# DEBUG.net
KiCad netlist of a schematic drawn in Altium Designer
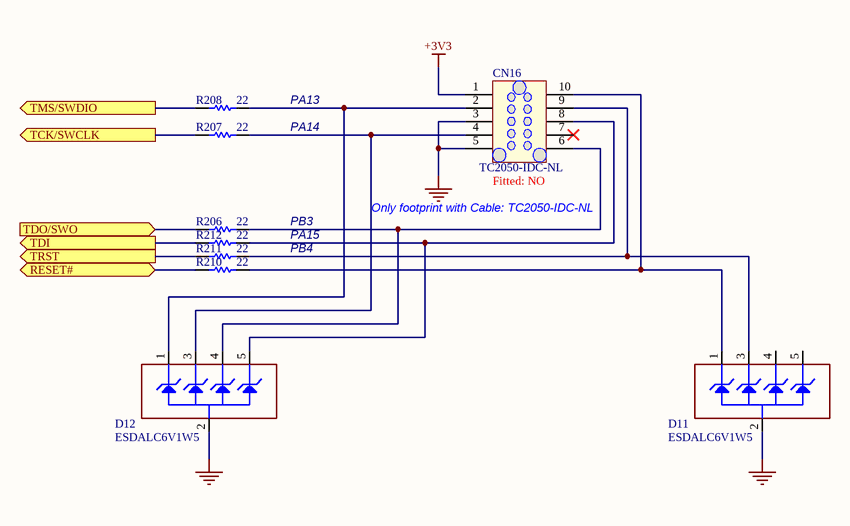
[diagram p0: DEBUG.SchDoc]

(export (version "E")
  (design (tool "Eeschema 10.0.6"))
  (components
    (comp (ref "CN16")
      (value "TC2050-IDC-NL")
      (footprint "TC2050-IDC-NL")
      (description "Tag_Connector Header, 10-Pin, Dual row No legs")
      (fields (field (name "FITTED") "NO"))
      (libsource (lib "MCD_TEMP_PCH") (part "Tag-10-C"))
    )
    (comp (ref "D11")
      (value "ESDALC6V1W5")
      (footprint "SC70-5")
      (description "Dual Transil array for ESD protection")
      (libsource (lib "MB1167_1") (part "ESDALC6V1W5"))
    )
    (comp (ref "D12")
      (value "ESDALC6V1W5")
      (footprint "SC70-5")
      (description "Dual Transil array for ESD protection")
      (libsource (lib "MB1167_1") (part "ESDALC6V1W5"))
    )
    (comp (ref "R206")
      (value "22")
      (footprint "0603R")
      (description "Resistor")
      (fields (field (name "PUBLISHER") "Altium Limited"))
      (libsource (lib "Miscellaneous Devices") (part "Res1"))
    )
    (comp (ref "R207")
      (value "22")
      (footprint "0603R")
      (description "Resistor")
      (fields (field (name "PUBLISHER") "Altium Limited"))
      (libsource (lib "Miscellaneous Devices") (part "Res1"))
    )
    (comp (ref "R208")
      (value "22")
      (footprint "0603R")
      (description "Resistor")
      (fields (field (name "PUBLISHER") "Altium Limited"))
      (libsource (lib "Miscellaneous Devices") (part "Res1"))
    )
    (comp (ref "R210")
      (value "22")
      (footprint "0603R")
      (description "Resistor")
      (fields (field (name "PUBLISHER") "Altium Limited"))
      (libsource (lib "Miscellaneous Devices") (part "Res1"))
    )
    (comp (ref "R211")
      (value "22")
      (footprint "0603R")
      (description "Resistor")
      (fields (field (name "PUBLISHER") "Altium Limited"))
      (libsource (lib "Miscellaneous Devices") (part "Res1"))
    )
    (comp (ref "R212")
      (value "22")
      (footprint "0603R")
      (description "Resistor")
      (fields (field (name "PUBLISHER") "Altium Limited"))
      (libsource (lib "Miscellaneous Devices") (part "Res1"))
    )
  )
  (nets
    (net (code "1") (name "+3V3") (class "Default")
      (node (ref "CN16") (pin "1") (pinfunction "1_1") (pintype "passive"))
    )
    (net (code "2") (name "/RESET#") (class "Default")
      (node (ref "R210") (pin "2") (pinfunction "2_2") (pintype "passive"))
    )
    (net (code "3") (name "/TCK{slash}SWCLK") (class "Default")
      (node (ref "R207") (pin "2") (pinfunction "2_2") (pintype "passive"))
    )
    (net (code "4") (name "/TDI") (class "Default")
      (node (ref "R212") (pin "2") (pinfunction "2_2") (pintype "passive"))
    )
    (net (code "5") (name "/TDO{slash}SWO") (class "Default")
      (node (ref "R206") (pin "2") (pinfunction "2_2") (pintype "passive"))
    )
    (net (code "6") (name "/TMS{slash}SWDIO") (class "Default")
      (node (ref "R208") (pin "2") (pinfunction "2_2") (pintype "passive"))
    )
    (net (code "7") (name "/TRST") (class "Default")
      (node (ref "R211") (pin "2") (pinfunction "2_2") (pintype "passive"))
    )
    (net (code "8") (name "GND") (class "Default")
      (node (ref "CN16") (pin "3") (pinfunction "3_3") (pintype "passive"))
      (node (ref "CN16") (pin "5") (pinfunction "5_5") (pintype "passive"))
      (node (ref "D11") (pin "2") (pinfunction "GND_2") (pintype "passive"))
      (node (ref "D12") (pin "2") (pinfunction "GND_2") (pintype "passive"))
    )
    (net (code "9") (name "Net-(D11-IO1)") (class "Default")
      (node (ref "CN16") (pin "10") (pinfunction "10_10") (pintype "passive"))
      (node (ref "D11") (pin "1") (pinfunction "IO1_1") (pintype "passive"))
      (node (ref "R210") (pin "1") (pinfunction "1_1") (pintype "passive"))
    )
    (net (code "10") (name "Net-(D11-IO2)") (class "Default")
      (node (ref "CN16") (pin "9") (pinfunction "9_9") (pintype "passive"))
      (node (ref "D11") (pin "3") (pinfunction "IO2_3") (pintype "passive"))
      (node (ref "R211") (pin "1") (pinfunction "1_1") (pintype "passive"))
    )
    (net (code "11") (name "Net-(D12-IO1)") (class "Default")
      (node (ref "CN16") (pin "2") (pinfunction "2_2") (pintype "passive"))
      (node (ref "D12") (pin "1") (pinfunction "IO1_1") (pintype "passive"))
      (node (ref "R208") (pin "1") (pinfunction "1_1") (pintype "passive"))
    )
    (net (code "12") (name "Net-(D12-IO2)") (class "Default")
      (node (ref "CN16") (pin "4") (pinfunction "4_4") (pintype "passive"))
      (node (ref "D12") (pin "3") (pinfunction "IO2_3") (pintype "passive"))
      (node (ref "R207") (pin "1") (pinfunction "1_1") (pintype "passive"))
    )
    (net (code "13") (name "Net-(D12-IO3)") (class "Default")
      (node (ref "CN16") (pin "6") (pinfunction "6_6") (pintype "passive"))
      (node (ref "D12") (pin "4") (pinfunction "IO3_4") (pintype "passive"))
      (node (ref "R206") (pin "1") (pinfunction "1_1") (pintype "passive"))
    )
    (net (code "14") (name "Net-(D12-IO4)") (class "Default")
      (node (ref "CN16") (pin "8") (pinfunction "8_8") (pintype "passive"))
      (node (ref "D12") (pin "5") (pinfunction "IO4_5") (pintype "passive"))
      (node (ref "R212") (pin "1") (pinfunction "1_1") (pintype "passive"))
    )
    (net (code "15") (name "unconnected-(CN16-Pad7)") (class "Default")
      (node (ref "CN16") (pin "7") (pinfunction "7_7") (pintype "passive+no_connect"))
    )
    (net (code "16") (name "unconnected-(D11-IO3-Pad4)") (class "Default")
      (node (ref "D11") (pin "4") (pinfunction "IO3_4") (pintype "passive"))
    )
    (net (code "17") (name "unconnected-(D11-IO4-Pad5)") (class "Default")
      (node (ref "D11") (pin "5") (pinfunction "IO4_5") (pintype "passive"))
    )
  )
)
